# citizen-scientist-attachment-1.net
KiCad netlist of a schematic drawn in EAGLE
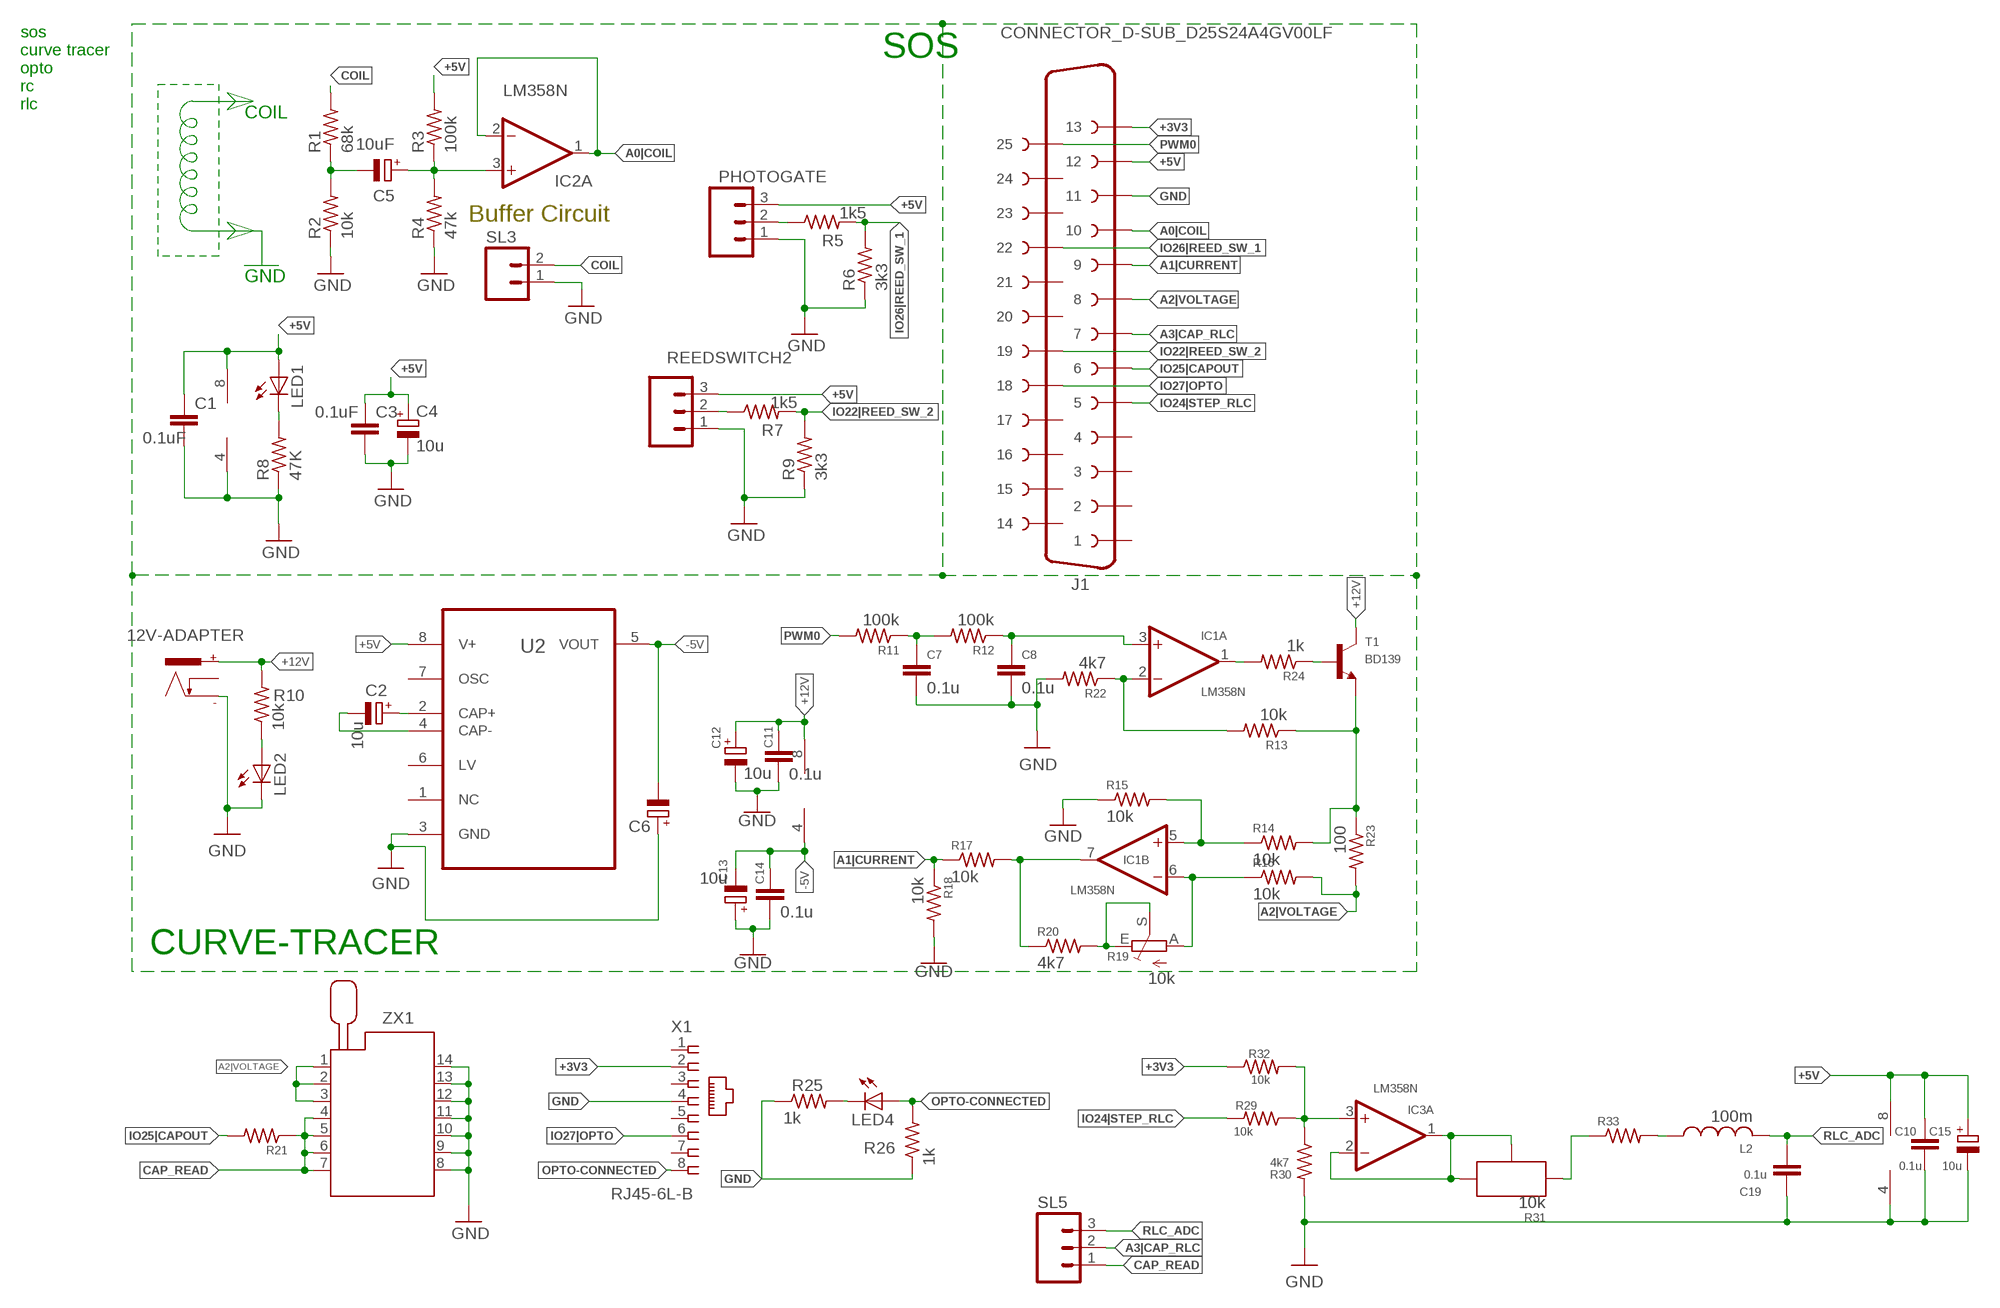
[diagram p0: schematic, sheet 1]

(export (version "E")
  (design (tool "Eeschema 10.0.6"))
  (components
    (comp (ref "12V-ADAPTER")
      (value "POWER_CON")
      (footprint "eagle-import:NEB21R")
      (libsource (lib "eagle-import") (part "POWER_CON"))
    )
    (comp (ref "C1")
      (value "0.1uF")
      (footprint "eagle-import:C025-025X050")
      (libsource (lib "eagle-import") (part "C-EU025-025X050"))
    )
    (comp (ref "C2")
      (value "10u")
      (footprint "eagle-import:TT2D5")
      (libsource (lib "eagle-import") (part "CPOL-EUTT2D5"))
    )
    (comp (ref "C3")
      (value "0.1uF")
      (footprint "eagle-import:C025-025X050")
      (libsource (lib "eagle-import") (part "C-EU025-025X050"))
    )
    (comp (ref "C4")
      (value "10u")
      (footprint "eagle-import:E2,5-6")
      (libsource (lib "eagle-import") (part "CPOL-EUE2.5-6"))
    )
    (comp (ref "C5")
      (value "10uF")
      (footprint "eagle-import:E2,5-6")
      (libsource (lib "eagle-import") (part "CPOL-EUE2.5-6"))
    )
    (comp (ref "C6")
      (value "CPOL-EUTT2D5")
      (footprint "eagle-import:TT2D5")
      (libsource (lib "eagle-import") (part "CPOL-EUTT2D5"))
    )
    (comp (ref "C7")
      (value "0.1u")
      (footprint "eagle-import:C025-025X050")
      (libsource (lib "eagle-import") (part "rcl_334_C-EU025-025X050"))
    )
    (comp (ref "C8")
      (value "0.1u")
      (footprint "eagle-import:C025-025X050")
      (libsource (lib "eagle-import") (part "rcl_334_C-EU025-025X050"))
    )
    (comp (ref "C10")
      (value "0.1u")
      (footprint "eagle-import:C025-025X050")
      (libsource (lib "eagle-import") (part "rcl_334_C-EU025-025X050"))
    )
    (comp (ref "C11")
      (value "0.1u")
      (footprint "eagle-import:C025-025X050")
      (libsource (lib "eagle-import") (part "rcl_334_C-EU025-025X050"))
    )
    (comp (ref "C12")
      (value "10u")
      (footprint "eagle-import:TT2D5")
      (libsource (lib "eagle-import") (part "CPOL-EUTT2D5"))
    )
    (comp (ref "C13")
      (value "10u")
      (footprint "eagle-import:TT2D5")
      (libsource (lib "eagle-import") (part "CPOL-EUTT2D5"))
    )
    (comp (ref "C14")
      (value "0.1u")
      (footprint "eagle-import:C025-025X050")
      (libsource (lib "eagle-import") (part "rcl_334_C-EU025-025X050"))
    )
    (comp (ref "C15")
      (value "10u")
      (footprint "eagle-import:TT2D5")
      (libsource (lib "eagle-import") (part "CPOL-EUTT2D5"))
    )
    (comp (ref "C19")
      (value "0.1u")
      (footprint "eagle-import:C025-025X050")
      (libsource (lib "eagle-import") (part "rcl_334_C-EU025-025X050"))
    )
    (comp (ref "IC1")
      (value "LM358N")
      (footprint "eagle-import:DIL08")
      (libsource (lib "eagle-import") (part "LM358N"))
    )
    (comp (ref "IC2")
      (value "LM358N")
      (footprint "eagle-import:DIL08")
      (libsource (lib "eagle-import") (part "LM358N"))
    )
    (comp (ref "IC3")
      (value "LM358N")
      (footprint "eagle-import:DIL08")
      (libsource (lib "eagle-import") (part "LM358N"))
    )
    (comp (ref "J1")
      (value "CONNECTOR_D-SUB_D25S24A4GV00LF")
      (footprint "eagle-import:CONNECTOR_D-SUB_D25S24A4GV00LF")
      (fields (field (name "MANUFACTURER") "amphenol-icc") (field (name "MPN") "D25S24A4GV00LF"))
      (libsource (lib "eagle-import") (part "CONNECTOR_D-SUB_D25S24A4GV00LF"))
    )
    (comp (ref "L2")
      (value "100m")
      (footprint "eagle-import:6000-XXXX-RC")
      (libsource (lib "eagle-import") (part "L-US6000-XXX-RC"))
    )
    (comp (ref "LED1")
      (value "LED3MM")
      (footprint "eagle-import:LED3MM")
      (libsource (lib "eagle-import") (part "LED3MM"))
    )
    (comp (ref "LED2")
      (value "LED3MM")
      (footprint "eagle-import:LED3MM")
      (libsource (lib "eagle-import") (part "LED3MM"))
    )
    (comp (ref "LED4")
      (value "LED3MM")
      (footprint "eagle-import:LED3MM")
      (libsource (lib "eagle-import") (part "LED3MM"))
    )
    (comp (ref "PHOTOGATE")
      (value "M03")
      (footprint "eagle-import:03P")
      (libsource (lib "eagle-import") (part "M03"))
    )
    (comp (ref "R1")
      (value "68k")
      (footprint "eagle-import:0204_7")
      (libsource (lib "eagle-import") (part "R-US_0204/7"))
    )
    (comp (ref "R2")
      (value "10k")
      (footprint "eagle-import:0204_7")
      (libsource (lib "eagle-import") (part "R-US_0204/7"))
    )
    (comp (ref "R3")
      (value "100k")
      (footprint "eagle-import:0204_7")
      (libsource (lib "eagle-import") (part "R-US_0204/7"))
    )
    (comp (ref "R4")
      (value "47k")
      (footprint "eagle-import:0204_7")
      (libsource (lib "eagle-import") (part "R-US_0204/7"))
    )
    (comp (ref "R5")
      (value "1k5")
      (footprint "eagle-import:0204_7")
      (libsource (lib "eagle-import") (part "R-US_0204/7"))
    )
    (comp (ref "R6")
      (value "3k3")
      (footprint "eagle-import:0204_7")
      (libsource (lib "eagle-import") (part "R-US_0204/7"))
    )
    (comp (ref "R7")
      (value "1k5")
      (footprint "eagle-import:0204_7")
      (libsource (lib "eagle-import") (part "R-US_0204/7"))
    )
    (comp (ref "R8")
      (value "47K")
      (footprint "eagle-import:0204_7")
      (libsource (lib "eagle-import") (part "R-US_0204/7"))
    )
    (comp (ref "R9")
      (value "3k3")
      (footprint "eagle-import:0204_7")
      (libsource (lib "eagle-import") (part "R-US_0204/7"))
    )
    (comp (ref "R10")
      (value "10k")
      (footprint "eagle-import:0204_7")
      (libsource (lib "eagle-import") (part "R-US_0204/7"))
    )
    (comp (ref "R11")
      (value "100k")
      (footprint "eagle-import:0204_7")
      (libsource (lib "eagle-import") (part "R-US_0204/7"))
    )
    (comp (ref "R12")
      (value "100k")
      (footprint "eagle-import:0204_7")
      (libsource (lib "eagle-import") (part "R-US_0204/7"))
    )
    (comp (ref "R13")
      (value "10k")
      (footprint "eagle-import:0207_10")
      (libsource (lib "eagle-import") (part "R-US_0207/10"))
    )
    (comp (ref "R14")
      (value "10k")
      (footprint "eagle-import:0207_10")
      (libsource (lib "eagle-import") (part "R-US_0207/10"))
    )
    (comp (ref "R15")
      (value "10k")
      (footprint "eagle-import:0207_10")
      (libsource (lib "eagle-import") (part "R-US_0207/10"))
    )
    (comp (ref "R16")
      (value "10k")
      (footprint "eagle-import:0207_10")
      (libsource (lib "eagle-import") (part "R-US_0207/10"))
    )
    (comp (ref "R17")
      (value "10k")
      (footprint "eagle-import:0207_10")
      (libsource (lib "eagle-import") (part "R-US_0207/10"))
    )
    (comp (ref "R18")
      (value "10k")
      (footprint "eagle-import:0207_10")
      (libsource (lib "eagle-import") (part "R-US_0207/10"))
    )
    (comp (ref "R19")
      (value "10k")
      (footprint "eagle-import:RJ9W")
      (libsource (lib "eagle-import") (part "TRIM_EU-RJ9W"))
    )
    (comp (ref "R20")
      (value "4k7")
      (footprint "eagle-import:0204_7")
      (libsource (lib "eagle-import") (part "R-US_0204/7"))
    )
    (comp (ref "R21")
      (value "R-US_0204/7")
      (footprint "eagle-import:0204_7")
      (libsource (lib "eagle-import") (part "R-US_0204/7"))
    )
    (comp (ref "R22")
      (value "4k7")
      (footprint "eagle-import:0207_10")
      (libsource (lib "eagle-import") (part "R-US_0207/10"))
    )
    (comp (ref "R23")
      (value "100")
      (footprint "eagle-import:0207_10")
      (libsource (lib "eagle-import") (part "R-US_0207/10"))
    )
    (comp (ref "R24")
      (value "1k")
      (footprint "eagle-import:0204_7")
      (libsource (lib "eagle-import") (part "R-US_0204/7"))
    )
    (comp (ref "R25")
      (value "1k")
      (footprint "eagle-import:0204_7")
      (libsource (lib "eagle-import") (part "R-US_0204/7"))
    )
    (comp (ref "R26")
      (value "1k")
      (footprint "eagle-import:0204_7")
      (libsource (lib "eagle-import") (part "R-US_0204/7"))
    )
    (comp (ref "R29")
      (value "10k")
      (footprint "eagle-import:0204_7")
      (libsource (lib "eagle-import") (part "R-US_0204/7"))
    )
    (comp (ref "R30")
      (value "4k7")
      (footprint "eagle-import:0207_10")
      (libsource (lib "eagle-import") (part "R-US_0207/10"))
    )
    (comp (ref "R31")
      (value "10k")
      (footprint "eagle-import:RJ9W")
      (libsource (lib "eagle-import") (part "POTNORMAL"))
    )
    (comp (ref "R32")
      (value "10k")
      (footprint "eagle-import:0207_10")
      (libsource (lib "eagle-import") (part "R-US_0207/10"))
    )
    (comp (ref "R33")
      (value "R-US_0204/7")
      (footprint "eagle-import:0204_7")
      (libsource (lib "eagle-import") (part "R-US_0204/7"))
    )
    (comp (ref "REEDSWITCH2")
      (value "M03")
      (footprint "eagle-import:03P")
      (libsource (lib "eagle-import") (part "M03"))
    )
    (comp (ref "SL3")
      (value "M02")
      (footprint "eagle-import:02P")
      (libsource (lib "eagle-import") (part "M02"))
    )
    (comp (ref "SL5")
      (value "M03")
      (footprint "eagle-import:03P")
      (libsource (lib "eagle-import") (part "M03"))
    )
    (comp (ref "T1")
      (value "BD139")
      (footprint "eagle-import:TO126")
      (libsource (lib "eagle-import") (part "BD139"))
    )
    (comp (ref "U2")
      (value "ICL7660CPAZ_ICL7660CPAZ")
      (footprint "eagle-import:ICL7660CPAZ_DIP254P762X533-8")
      (fields (field (name "MF") "Renesas Electronics") (field (name "MP") "ICL7660CPAZ"))
      (libsource (lib "eagle-import") (part "ICL7660CPAZ_ICL7660CPAZ"))
    )
    (comp (ref "X1")
      (value "RJ45-6L-B")
      (footprint "eagle-import:RJ45-NO-SHIELD")
      (libsource (lib "eagle-import") (part "RJ45-6L-B"))
    )
    (comp (ref "ZX1")
      (value "214-3339-00-0602J")
      (footprint "eagle-import:214-3339-00-0602J")
      (fields (field (name "MF") "3M"))
      (libsource (lib "eagle-import") (part "214-3339-00-0602J"))
    )
  )
  (nets
    (net (code "1") (name "+3V3") (class "Default")
      (node (ref "J1") (pin "P$13") (pinfunction "13_P$13") (pintype "passive"))
      (node (ref "R32") (pin "1") (pinfunction "1_1") (pintype "passive"))
      (node (ref "X1") (pin "2") (pinfunction "2_2") (pintype "passive"))
    )
    (net (code "2") (name "+5V") (class "Default")
      (node (ref "C1") (pin "1") (pinfunction "1_1") (pintype "passive"))
      (node (ref "C10") (pin "1") (pinfunction "1_1") (pintype "passive"))
      (node (ref "C15") (pin "+") (pinfunction "+_+") (pintype "passive"))
      (node (ref "C3") (pin "1") (pinfunction "1_1") (pintype "passive"))
      (node (ref "C4") (pin "+") (pinfunction "+_+") (pintype "passive"))
      (node (ref "IC2") (pin "8") (pinfunction "V+_8") (pintype "power_in"))
      (node (ref "IC3") (pin "8") (pinfunction "V+_8") (pintype "power_in"))
      (node (ref "J1") (pin "P$14") (pinfunction "12_P$14") (pintype "passive"))
      (node (ref "LED1") (pin "A") (pinfunction "A_A") (pintype "passive"))
      (node (ref "PHOTOGATE") (pin "3") (pinfunction "3_3") (pintype "passive"))
      (node (ref "R3") (pin "2") (pinfunction "2_2") (pintype "passive"))
      (node (ref "REEDSWITCH2") (pin "3") (pinfunction "3_3") (pintype "passive"))
      (node (ref "U2") (pin "8") (pinfunction "V+_8") (pintype "power_in"))
    )
    (net (code "3") (name "+12V") (class "Default")
      (node (ref "12V-ADAPTER") (pin "+") (pinfunction "+_+") (pintype "passive"))
      (node (ref "C11") (pin "1") (pinfunction "1_1") (pintype "passive"))
      (node (ref "C12") (pin "+") (pinfunction "+_+") (pintype "passive"))
      (node (ref "IC1") (pin "8") (pinfunction "V+_8") (pintype "power_in"))
      (node (ref "R10") (pin "2") (pinfunction "2_2") (pintype "passive"))
      (node (ref "T1") (pin "2") (pinfunction "C_2") (pintype "passive"))
    )
    (net (code "4") (name "-5V") (class "Default")
      (node (ref "C13") (pin "-") (pinfunction "-_-") (pintype "passive"))
      (node (ref "C14") (pin "1") (pinfunction "1_1") (pintype "passive"))
      (node (ref "C6") (pin "-") (pinfunction "-_-") (pintype "passive"))
      (node (ref "IC1") (pin "4") (pinfunction "V-_4") (pintype "power_in"))
      (node (ref "U2") (pin "5") (pinfunction "VOUT_5") (pintype "output"))
    )
    (net (code "5") (name "A0|COIL") (class "Default")
      (node (ref "IC2") (pin "1") (pinfunction "OUT_1") (pintype "output"))
      (node (ref "IC2") (pin "2") (pinfunction "-IN_2") (pintype "input"))
      (node (ref "J1") (pin "P$16") (pinfunction "10_P$16") (pintype "passive"))
    )
    (net (code "6") (name "A1|CURRENT") (class "Default")
      (node (ref "J1") (pin "P$17") (pinfunction "9_P$17") (pintype "passive"))
      (node (ref "R17") (pin "1") (pinfunction "1_1") (pintype "passive"))
      (node (ref "R18") (pin "1") (pinfunction "1_1") (pintype "passive"))
    )
    (net (code "7") (name "A2|VOLTAGE") (class "Default")
      (node (ref "J1") (pin "P$18") (pinfunction "8_P$18") (pintype "passive"))
      (node (ref "R16") (pin "2") (pinfunction "2_2") (pintype "passive"))
      (node (ref "R23") (pin "2") (pinfunction "2_2") (pintype "passive"))
      (node (ref "ZX1") (pin "1") (pinfunction "1_1") (pintype "passive"))
      (node (ref "ZX1") (pin "2") (pinfunction "2_2") (pintype "passive"))
      (node (ref "ZX1") (pin "3") (pinfunction "3_3") (pintype "passive"))
    )
    (net (code "8") (name "A3|CAP_RLC") (class "Default")
      (node (ref "J1") (pin "P$19") (pinfunction "7_P$19") (pintype "passive"))
      (node (ref "SL5") (pin "2") (pinfunction "2_2") (pintype "passive"))
    )
    (net (code "9") (name "CAP_READ") (class "Default")
      (node (ref "R21") (pin "1") (pinfunction "1_1") (pintype "passive"))
      (node (ref "SL5") (pin "1") (pinfunction "1_1") (pintype "passive"))
      (node (ref "ZX1") (pin "4") (pinfunction "4_4") (pintype "passive"))
      (node (ref "ZX1") (pin "5") (pinfunction "5_5") (pintype "passive"))
      (node (ref "ZX1") (pin "6") (pinfunction "6_6") (pintype "passive"))
      (node (ref "ZX1") (pin "7") (pinfunction "7_7") (pintype "passive"))
    )
    (net (code "10") (name "COIL") (class "Default")
      (node (ref "R1") (pin "2") (pinfunction "2_2") (pintype "passive"))
      (node (ref "SL3") (pin "2") (pinfunction "2_2") (pintype "passive"))
    )
    (net (code "11") (name "GND") (class "Default")
      (node (ref "12V-ADAPTER") (pin "-") (pinfunction "-_-") (pintype "passive"))
      (node (ref "C1") (pin "2") (pinfunction "2_2") (pintype "passive"))
      (node (ref "C10") (pin "2") (pinfunction "2_2") (pintype "passive"))
      (node (ref "C11") (pin "2") (pinfunction "2_2") (pintype "passive"))
      (node (ref "C12") (pin "-") (pinfunction "-_-") (pintype "passive"))
      (node (ref "C13") (pin "+") (pinfunction "+_+") (pintype "passive"))
      (node (ref "C14") (pin "2") (pinfunction "2_2") (pintype "passive"))
      (node (ref "C15") (pin "-") (pinfunction "-_-") (pintype "passive"))
      (node (ref "C19") (pin "2") (pinfunction "2_2") (pintype "passive"))
      (node (ref "C3") (pin "2") (pinfunction "2_2") (pintype "passive"))
      (node (ref "C4") (pin "-") (pinfunction "-_-") (pintype "passive"))
      (node (ref "C6") (pin "+") (pinfunction "+_+") (pintype "passive"))
      (node (ref "C7") (pin "2") (pinfunction "2_2") (pintype "passive"))
      (node (ref "C8") (pin "2") (pinfunction "2_2") (pintype "passive"))
      (node (ref "IC2") (pin "4") (pinfunction "V-_4") (pintype "power_in"))
      (node (ref "IC3") (pin "4") (pinfunction "V-_4") (pintype "power_in"))
      (node (ref "J1") (pin "P$15") (pinfunction "11_P$15") (pintype "passive"))
      (node (ref "LED2") (pin "K") (pinfunction "C_K") (pintype "passive"))
      (node (ref "PHOTOGATE") (pin "1") (pinfunction "1_1") (pintype "passive"))
      (node (ref "R15") (pin "1") (pinfunction "1_1") (pintype "passive"))
      (node (ref "R18") (pin "2") (pinfunction "2_2") (pintype "passive"))
      (node (ref "R2") (pin "1") (pinfunction "1_1") (pintype "passive"))
      (node (ref "R22") (pin "2") (pinfunction "2_2") (pintype "passive"))
      (node (ref "R25") (pin "1") (pinfunction "1_1") (pintype "passive"))
      (node (ref "R26") (pin "1") (pinfunction "1_1") (pintype "passive"))
      (node (ref "R30") (pin "2") (pinfunction "2_2") (pintype "passive"))
      (node (ref "R4") (pin "1") (pinfunction "1_1") (pintype "passive"))
      (node (ref "R6") (pin "1") (pinfunction "1_1") (pintype "passive"))
      (node (ref "R8") (pin "1") (pinfunction "1_1") (pintype "passive"))
      (node (ref "R9") (pin "1") (pinfunction "1_1") (pintype "passive"))
      (node (ref "REEDSWITCH2") (pin "1") (pinfunction "1_1") (pintype "passive"))
      (node (ref "SL3") (pin "1") (pinfunction "1_1") (pintype "passive"))
      (node (ref "U2") (pin "3") (pinfunction "GND_3") (pintype "passive"))
      (node (ref "X1") (pin "4") (pinfunction "4_4") (pintype "passive"))
      (node (ref "ZX1") (pin "10") (pinfunction "10_10") (pintype "passive"))
      (node (ref "ZX1") (pin "11") (pinfunction "11_11") (pintype "passive"))
      (node (ref "ZX1") (pin "12") (pinfunction "12_12") (pintype "passive"))
      (node (ref "ZX1") (pin "13") (pinfunction "13_13") (pintype "passive"))
      (node (ref "ZX1") (pin "14") (pinfunction "14_14") (pintype "passive"))
      (node (ref "ZX1") (pin "8") (pinfunction "8_8") (pintype "passive"))
      (node (ref "ZX1") (pin "9") (pinfunction "9_9") (pintype "passive"))
    )
    (net (code "12") (name "IO22|REED_SW_2") (class "Default")
      (node (ref "J1") (pin "P$7") (pinfunction "19_P$7") (pintype "passive"))
      (node (ref "R7") (pin "2") (pinfunction "2_2") (pintype "passive"))
      (node (ref "R9") (pin "2") (pinfunction "2_2") (pintype "passive"))
    )
    (net (code "13") (name "IO24|STEP_RLC") (class "Default")
      (node (ref "J1") (pin "P$21") (pinfunction "5_P$21") (pintype "passive"))
      (node (ref "R29") (pin "2") (pinfunction "2_2") (pintype "passive"))
    )
    (net (code "14") (name "IO25|CAPOUT") (class "Default")
      (node (ref "J1") (pin "P$20") (pinfunction "6_P$20") (pintype "passive"))
      (node (ref "R21") (pin "2") (pinfunction "2_2") (pintype "passive"))
    )
    (net (code "15") (name "IO26|REED_SW_1") (class "Default")
      (node (ref "J1") (pin "P$4") (pinfunction "22_P$4") (pintype "passive"))
      (node (ref "R5") (pin "2") (pinfunction "2_2") (pintype "passive"))
      (node (ref "R6") (pin "2") (pinfunction "2_2") (pintype "passive"))
    )
    (net (code "16") (name "IO27|OPTO") (class "Default")
      (node (ref "J1") (pin "P$8") (pinfunction "18_P$8") (pintype "passive"))
      (node (ref "X1") (pin "6") (pinfunction "6_6") (pintype "passive"))
    )
    (net (code "17") (name "Net-(C5-Pad-)") (class "Default")
      (node (ref "C5") (pin "-") (pinfunction "-_-") (pintype "passive"))
      (node (ref "R1") (pin "1") (pinfunction "1_1") (pintype "passive"))
      (node (ref "R2") (pin "2") (pinfunction "2_2") (pintype "passive"))
    )
    (net (code "18") (name "Net-(C7-Pad1)") (class "Default")
      (node (ref "C7") (pin "1") (pinfunction "1_1") (pintype "passive"))
      (node (ref "R11") (pin "1") (pinfunction "1_1") (pintype "passive"))
      (node (ref "R12") (pin "2") (pinfunction "2_2") (pintype "passive"))
    )
    (net (code "19") (name "Net-(IC1A-+IN)") (class "Default")
      (node (ref "C8") (pin "1") (pinfunction "1_1") (pintype "passive"))
      (node (ref "IC1") (pin "3") (pinfunction "+IN_3") (pintype "input"))
      (node (ref "R12") (pin "1") (pinfunction "1_1") (pintype "passive"))
    )
    (net (code "20") (name "Net-(IC1A--IN)") (class "Default")
      (node (ref "IC1") (pin "2") (pinfunction "-IN_2") (pintype "input"))
      (node (ref "R13") (pin "2") (pinfunction "2_2") (pintype "passive"))
      (node (ref "R22") (pin "1") (pinfunction "1_1") (pintype "passive"))
    )
    (net (code "21") (name "Net-(IC1A-OUT)") (class "Default")
      (node (ref "IC1") (pin "1") (pinfunction "OUT_1") (pintype "output"))
      (node (ref "R24") (pin "2") (pinfunction "2_2") (pintype "passive"))
    )
    (net (code "22") (name "Net-(IC1B-+IN)") (class "Default")
      (node (ref "IC1") (pin "5") (pinfunction "+IN_5") (pintype "input"))
      (node (ref "R14") (pin "1") (pinfunction "1_1") (pintype "passive"))
      (node (ref "R15") (pin "2") (pinfunction "2_2") (pintype "passive"))
    )
    (net (code "23") (name "Net-(IC1B--IN)") (class "Default")
      (node (ref "IC1") (pin "6") (pinfunction "-IN_6") (pintype "input"))
      (node (ref "R16") (pin "1") (pinfunction "1_1") (pintype "passive"))
      (node (ref "R19") (pin "A") (pinfunction "A_A") (pintype "passive"))
    )
    (net (code "24") (name "Net-(IC1B-OUT)") (class "Default")
      (node (ref "IC1") (pin "7") (pinfunction "OUT_7") (pintype "output"))
      (node (ref "R17") (pin "2") (pinfunction "2_2") (pintype "passive"))
      (node (ref "R20") (pin "1") (pinfunction "1_1") (pintype "passive"))
    )
    (net (code "25") (name "Net-(IC2A-+IN)") (class "Default")
      (node (ref "C5") (pin "+") (pinfunction "+_+") (pintype "passive"))
      (node (ref "IC2") (pin "3") (pinfunction "+IN_3") (pintype "input"))
      (node (ref "R3") (pin "1") (pinfunction "1_1") (pintype "passive"))
      (node (ref "R4") (pin "2") (pinfunction "2_2") (pintype "passive"))
    )
    (net (code "26") (name "Net-(IC3A-+IN)") (class "Default")
      (node (ref "IC3") (pin "3") (pinfunction "+IN_3") (pintype "input"))
      (node (ref "R29") (pin "1") (pinfunction "1_1") (pintype "passive"))
      (node (ref "R30") (pin "1") (pinfunction "1_1") (pintype "passive"))
      (node (ref "R32") (pin "2") (pinfunction "2_2") (pintype "passive"))
    )
    (net (code "27") (name "Net-(IC3A--IN)") (class "Default")
      (node (ref "IC3") (pin "1") (pinfunction "OUT_1") (pintype "output"))
      (node (ref "IC3") (pin "2") (pinfunction "-IN_2") (pintype "input"))
      (node (ref "R31") (pin "A") (pinfunction "A_A") (pintype "passive"))
      (node (ref "R31") (pin "S") (pinfunction "S_S") (pintype "passive"))
    )
    (net (code "28") (name "Net-(L2-Pad1)") (class "Default")
      (node (ref "L2") (pin "1") (pinfunction "1_1") (pintype "passive"))
      (node (ref "R33") (pin "2") (pinfunction "2_2") (pintype "passive"))
    )
    (net (code "29") (name "Net-(LED1-C)") (class "Default")
      (node (ref "LED1") (pin "K") (pinfunction "C_K") (pintype "passive"))
      (node (ref "R8") (pin "2") (pinfunction "2_2") (pintype "passive"))
    )
    (net (code "30") (name "Net-(LED2-PadA)") (class "Default")
      (node (ref "LED2") (pin "A") (pinfunction "A_A") (pintype "passive"))
      (node (ref "R10") (pin "1") (pinfunction "1_1") (pintype "passive"))
    )
    (net (code "31") (name "Net-(LED4-C)") (class "Default")
      (node (ref "LED4") (pin "K") (pinfunction "C_K") (pintype "passive"))
      (node (ref "R25") (pin "2") (pinfunction "2_2") (pintype "passive"))
    )
    (net (code "32") (name "Net-(PHOTOGATE-Pad2)") (class "Default")
      (node (ref "PHOTOGATE") (pin "2") (pinfunction "2_2") (pintype "passive"))
      (node (ref "R5") (pin "1") (pinfunction "1_1") (pintype "passive"))
    )
    (net (code "33") (name "Net-(R7-Pad1)") (class "Default")
      (node (ref "R7") (pin "1") (pinfunction "1_1") (pintype "passive"))
      (node (ref "REEDSWITCH2") (pin "2") (pinfunction "2_2") (pintype "passive"))
    )
    (net (code "34") (name "Net-(R19-PadE)") (class "Default")
      (node (ref "R19") (pin "E") (pinfunction "E_E") (pintype "passive"))
      (node (ref "R19") (pin "S") (pinfunction "S_S") (pintype "passive"))
      (node (ref "R20") (pin "2") (pinfunction "2_2") (pintype "passive"))
    )
    (net (code "35") (name "Net-(R31-PadE)") (class "Default")
      (node (ref "R31") (pin "E") (pinfunction "E_E") (pintype "passive"))
      (node (ref "R33") (pin "1") (pinfunction "1_1") (pintype "passive"))
    )
    (net (code "36") (name "Net-(T1-B)") (class "Default")
      (node (ref "R24") (pin "1") (pinfunction "1_1") (pintype "passive"))
      (node (ref "T1") (pin "3") (pinfunction "B_3") (pintype "passive"))
    )
    (net (code "37") (name "Net-(T1-E)") (class "Default")
      (node (ref "R13") (pin "1") (pinfunction "1_1") (pintype "passive"))
      (node (ref "R14") (pin "2") (pinfunction "2_2") (pintype "passive"))
      (node (ref "R23") (pin "1") (pinfunction "1_1") (pintype "passive"))
      (node (ref "T1") (pin "1") (pinfunction "E_1") (pintype "passive"))
    )
    (net (code "38") (name "Net-(U2-CAP+)") (class "Default")
      (node (ref "C2") (pin "+") (pinfunction "+_+") (pintype "passive"))
      (node (ref "U2") (pin "2") (pinfunction "CAP+_2") (pintype "input"))
    )
    (net (code "39") (name "Net-(U2-CAP-)") (class "Default")
      (node (ref "C2") (pin "-") (pinfunction "-_-") (pintype "passive"))
      (node (ref "U2") (pin "4") (pinfunction "CAP-_4") (pintype "input"))
    )
    (net (code "40") (name "OPTO-CONNECTED") (class "Default")
      (node (ref "LED4") (pin "A") (pinfunction "A_A") (pintype "passive"))
      (node (ref "R26") (pin "2") (pinfunction "2_2") (pintype "passive"))
      (node (ref "X1") (pin "8") (pinfunction "8_8") (pintype "passive"))
    )
    (net (code "41") (name "PWM0") (class "Default")
      (node (ref "J1") (pin "P$1") (pinfunction "25_P$1") (pintype "passive"))
      (node (ref "R11") (pin "2") (pinfunction "2_2") (pintype "passive"))
    )
    (net (code "42") (name "RLC_ADC") (class "Default")
      (node (ref "C19") (pin "1") (pinfunction "1_1") (pintype "passive"))
      (node (ref "L2") (pin "2") (pinfunction "2_2") (pintype "passive"))
      (node (ref "SL5") (pin "3") (pinfunction "3_3") (pintype "passive"))
    )
    (net (code "43") (name "unconnected-(12V-ADAPTER-PadC)") (class "Default")
      (node (ref "12V-ADAPTER") (pin "C") (pinfunction "C_C") (pintype "passive"))
    )
    (net (code "44") (name "unconnected-(J1-2-PadP$24)") (class "Default")
      (node (ref "J1") (pin "P$24") (pinfunction "2_P$24") (pintype "passive"))
    )
    (net (code "45") (name "unconnected-(J1-3-PadP$23)") (class "Default")
      (node (ref "J1") (pin "P$23") (pinfunction "3_P$23") (pintype "passive"))
    )
    (net (code "46") (name "unconnected-(J1-4-PadP$22)") (class "Default")
      (node (ref "J1") (pin "P$22") (pinfunction "4_P$22") (pintype "passive"))
    )
    (net (code "47") (name "unconnected-(J1-14-PadP$12)") (class "Default")
      (node (ref "J1") (pin "P$12") (pinfunction "14_P$12") (pintype "passive"))
    )
    (net (code "48") (name "unconnected-(J1-15-PadP$11)") (class "Default")
      (node (ref "J1") (pin "P$11") (pinfunction "15_P$11") (pintype "passive"))
    )
    (net (code "49") (name "unconnected-(J1-16-PadP$10)") (class "Default")
      (node (ref "J1") (pin "P$10") (pinfunction "16_P$10") (pintype "passive"))
    )
    (net (code "50") (name "unconnected-(J1-17-PadP$9)") (class "Default")
      (node (ref "J1") (pin "P$9") (pinfunction "17_P$9") (pintype "passive"))
    )
    (net (code "51") (name "unconnected-(J1-20-PadP$6)") (class "Default")
      (node (ref "J1") (pin "P$6") (pinfunction "20_P$6") (pintype "passive"))
    )
    (net (code "52") (name "unconnected-(J1-21-PadP$5)") (class "Default")
      (node (ref "J1") (pin "P$5") (pinfunction "21_P$5") (pintype "passive"))
    )
    (net (code "53") (name "unconnected-(J1-23-PadP$3)") (class "Default")
      (node (ref "J1") (pin "P$3") (pinfunction "23_P$3") (pintype "passive"))
    )
    (net (code "54") (name "unconnected-(J1-24-PadP$2)") (class "Default")
      (node (ref "J1") (pin "P$2") (pinfunction "24_P$2") (pintype "passive"))
    )
    (net (code "55") (name "unconnected-(J1-Pad1)") (class "Default")
      (node (ref "J1") (pin "1") (pinfunction "1_1") (pintype "passive"))
    )
    (net (code "56") (name "unconnected-(U2-LV-Pad6)") (class "Default")
      (node (ref "U2") (pin "6") (pinfunction "LV_6") (pintype "passive"))
    )
    (net (code "57") (name "unconnected-(U2-NC-Pad1)") (class "Default")
      (node (ref "U2") (pin "1") (pinfunction "NC_1") (pintype "no_connect"))
    )
    (net (code "58") (name "unconnected-(U2-OSC-Pad7)") (class "Default")
      (node (ref "U2") (pin "7") (pinfunction "OSC_7") (pintype "input"))
    )
    (net (code "59") (name "unconnected-(X1-Pad1)") (class "Default")
      (node (ref "X1") (pin "1") (pinfunction "1_1") (pintype "passive"))
    )
    (net (code "60") (name "unconnected-(X1-Pad3)") (class "Default")
      (node (ref "X1") (pin "3") (pinfunction "3_3") (pintype "passive"))
    )
    (net (code "61") (name "unconnected-(X1-Pad5)") (class "Default")
      (node (ref "X1") (pin "5") (pinfunction "5_5") (pintype "passive"))
    )
    (net (code "62") (name "unconnected-(X1-Pad7)") (class "Default")
      (node (ref "X1") (pin "7") (pinfunction "7_7") (pintype "passive"))
    )
  )
)
